# CurrentSources.net
KiCad netlist of a schematic drawn in Altium Designer
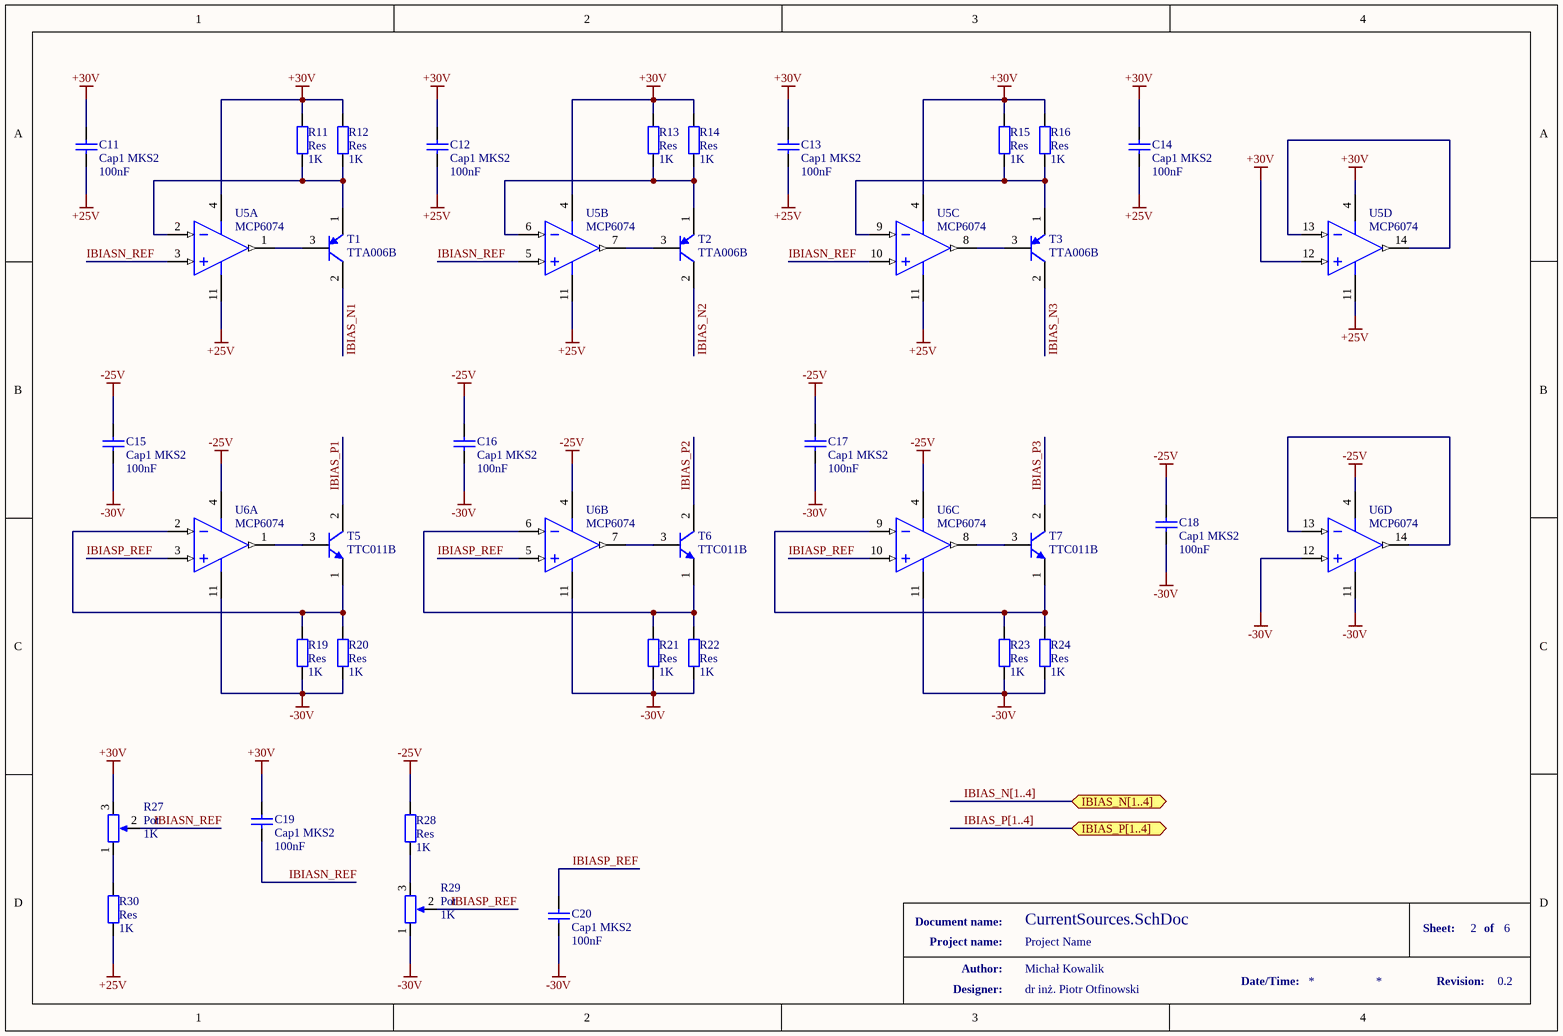
[diagram p0: CurrentSources.SchDoc]

(export (version "E")
  (design (tool "Eeschema 10.0.6"))
  (components
    (comp (ref "C11")
      (value "Cap1 MKS2")
      (footprint "CAP-0.5-WIMA_MKS2")
      (description "WIMA MKS2 Metallized Polyester (PET) \r\nCapacitors in PCM 5 mm")
      (fields (field (name "ALTIUM_VALUE") "100nF"))
      (libsource (lib "SchematicLib") (part "Cap1"))
    )
    (comp (ref "C12")
      (value "Cap1 MKS2")
      (footprint "CAP-0.5-WIMA_MKS2")
      (description "WIMA MKS2 Metallized Polyester (PET) \r\nCapacitors in PCM 5 mm")
      (fields (field (name "ALTIUM_VALUE") "100nF"))
      (libsource (lib "SchematicLib") (part "Cap1"))
    )
    (comp (ref "C13")
      (value "Cap1 MKS2")
      (footprint "CAP-0.5-WIMA_MKS2")
      (description "WIMA MKS2 Metallized Polyester (PET) \r\nCapacitors in PCM 5 mm")
      (fields (field (name "ALTIUM_VALUE") "100nF"))
      (libsource (lib "SchematicLib") (part "Cap1"))
    )
    (comp (ref "C14")
      (value "Cap1 MKS2")
      (footprint "CAP-0.5-WIMA_MKS2")
      (description "WIMA MKS2 Metallized Polyester (PET) \r\nCapacitors in PCM 5 mm")
      (fields (field (name "ALTIUM_VALUE") "100nF"))
      (libsource (lib "SchematicLib") (part "Cap1"))
    )
    (comp (ref "C15")
      (value "Cap1 MKS2")
      (footprint "CAP-0.5-WIMA_MKS2")
      (description "WIMA MKS2 Metallized Polyester (PET) \r\nCapacitors in PCM 5 mm")
      (fields (field (name "ALTIUM_VALUE") "100nF"))
      (libsource (lib "SchematicLib") (part "Cap1"))
    )
    (comp (ref "C16")
      (value "Cap1 MKS2")
      (footprint "CAP-0.5-WIMA_MKS2")
      (description "WIMA MKS2 Metallized Polyester (PET) \r\nCapacitors in PCM 5 mm")
      (fields (field (name "ALTIUM_VALUE") "100nF"))
      (libsource (lib "SchematicLib") (part "Cap1"))
    )
    (comp (ref "C17")
      (value "Cap1 MKS2")
      (footprint "CAP-0.5-WIMA_MKS2")
      (description "WIMA MKS2 Metallized Polyester (PET) \r\nCapacitors in PCM 5 mm")
      (fields (field (name "ALTIUM_VALUE") "100nF"))
      (libsource (lib "SchematicLib") (part "Cap1"))
    )
    (comp (ref "C18")
      (value "Cap1 MKS2")
      (footprint "CAP-0.5-WIMA_MKS2")
      (description "WIMA MKS2 Metallized Polyester (PET) \r\nCapacitors in PCM 5 mm")
      (fields (field (name "ALTIUM_VALUE") "100nF"))
      (libsource (lib "SchematicLib") (part "Cap1"))
    )
    (comp (ref "C19")
      (value "Cap1 MKS2")
      (footprint "CAP-0.5-WIMA_MKS2")
      (description "WIMA MKS2 Metallized Polyester (PET) \r\nCapacitors in PCM 5 mm")
      (fields (field (name "ALTIUM_VALUE") "100nF"))
      (libsource (lib "SchematicLib") (part "Cap1"))
    )
    (comp (ref "C20")
      (value "Cap1 MKS2")
      (footprint "CAP-0.5-WIMA_MKS2")
      (description "WIMA MKS2 Metallized Polyester (PET) \r\nCapacitors in PCM 5 mm")
      (fields (field (name "ALTIUM_VALUE") "100nF"))
      (libsource (lib "SchematicLib") (part "Cap1"))
    )
    (comp (ref "R11")
      (value "Res")
      (footprint "RESISTOR-10mm")
      (description "Resistor")
      (fields (field (name "ALTIUM_VALUE") "1K"))
      (libsource (lib "SchematicLib") (part "Res"))
    )
    (comp (ref "R12")
      (value "Res")
      (footprint "RESISTOR-10mm")
      (description "Resistor")
      (fields (field (name "ALTIUM_VALUE") "1K"))
      (libsource (lib "SchematicLib") (part "Res"))
    )
    (comp (ref "R13")
      (value "Res")
      (footprint "RESISTOR-10mm")
      (description "Resistor")
      (fields (field (name "ALTIUM_VALUE") "1K"))
      (libsource (lib "SchematicLib") (part "Res"))
    )
    (comp (ref "R14")
      (value "Res")
      (footprint "RESISTOR-10mm")
      (description "Resistor")
      (fields (field (name "ALTIUM_VALUE") "1K"))
      (libsource (lib "SchematicLib") (part "Res"))
    )
    (comp (ref "R15")
      (value "Res")
      (footprint "RESISTOR-10mm")
      (description "Resistor")
      (fields (field (name "ALTIUM_VALUE") "1K"))
      (libsource (lib "SchematicLib") (part "Res"))
    )
    (comp (ref "R16")
      (value "Res")
      (footprint "RESISTOR-10mm")
      (description "Resistor")
      (fields (field (name "ALTIUM_VALUE") "1K"))
      (libsource (lib "SchematicLib") (part "Res"))
    )
    (comp (ref "R19")
      (value "Res")
      (footprint "RESISTOR-10mm")
      (description "Resistor")
      (fields (field (name "ALTIUM_VALUE") "1K"))
      (libsource (lib "SchematicLib") (part "Res"))
    )
    (comp (ref "R20")
      (value "Res")
      (footprint "RESISTOR-10mm")
      (description "Resistor")
      (fields (field (name "ALTIUM_VALUE") "1K"))
      (libsource (lib "SchematicLib") (part "Res"))
    )
    (comp (ref "R21")
      (value "Res")
      (footprint "RESISTOR-10mm")
      (description "Resistor")
      (fields (field (name "ALTIUM_VALUE") "1K"))
      (libsource (lib "SchematicLib") (part "Res"))
    )
    (comp (ref "R22")
      (value "Res")
      (footprint "RESISTOR-10mm")
      (description "Resistor")
      (fields (field (name "ALTIUM_VALUE") "1K"))
      (libsource (lib "SchematicLib") (part "Res"))
    )
    (comp (ref "R23")
      (value "Res")
      (footprint "RESISTOR-10mm")
      (description "Resistor")
      (fields (field (name "ALTIUM_VALUE") "1K"))
      (libsource (lib "SchematicLib") (part "Res"))
    )
    (comp (ref "R24")
      (value "Res")
      (footprint "RESISTOR-10mm")
      (description "Resistor")
      (fields (field (name "ALTIUM_VALUE") "1K"))
      (libsource (lib "SchematicLib") (part "Res"))
    )
    (comp (ref "R27")
      (value "Pot")
      (footprint "T910W")
      (description "Potentiometer")
      (fields (field (name "ALTIUM_VALUE") "1K"))
      (libsource (lib "SchematicLib") (part "Pot"))
    )
    (comp (ref "R28")
      (value "Res")
      (footprint "RESISTOR-10mm")
      (description "Resistor")
      (fields (field (name "ALTIUM_VALUE") "1K"))
      (libsource (lib "SchematicLib") (part "Res"))
    )
    (comp (ref "R29")
      (value "Pot")
      (footprint "T910W")
      (description "Potentiometer")
      (fields (field (name "ALTIUM_VALUE") "1K"))
      (libsource (lib "SchematicLib") (part "Pot"))
    )
    (comp (ref "R30")
      (value "Res")
      (footprint "RESISTOR-10mm")
      (description "Resistor")
      (fields (field (name "ALTIUM_VALUE") "1K"))
      (libsource (lib "SchematicLib") (part "Res"))
    )
    (comp (ref "T1")
      (value "TTA006B")
      (footprint "TO-126")
      (description "PNP High Voltage Transistor")
      (libsource (lib "SchematicLib") (part "TTA006B"))
    )
    (comp (ref "T2")
      (value "TTA006B")
      (footprint "TO-126")
      (description "PNP High Voltage Transistor")
      (libsource (lib "SchematicLib") (part "TTA006B"))
    )
    (comp (ref "T3")
      (value "TTA006B")
      (footprint "TO-126")
      (description "PNP High Voltage Transistor")
      (libsource (lib "SchematicLib") (part "TTA006B"))
    )
    (comp (ref "T5")
      (value "TTC011B")
      (footprint "TO-126")
      (description "NPN High Voltage Transistor")
      (libsource (lib "SchematicLib") (part "TTC011B"))
    )
    (comp (ref "T6")
      (value "TTC011B")
      (footprint "TO-126")
      (description "NPN High Voltage Transistor")
      (libsource (lib "SchematicLib") (part "TTC011B"))
    )
    (comp (ref "T7")
      (value "TTC011B")
      (footprint "TO-126")
      (description "NPN High Voltage Transistor")
      (libsource (lib "SchematicLib") (part "TTC011B"))
    )
    (comp (ref "U5")
      (value "MCP6074")
      (footprint "SO_14_IPC_MD")
      (description "110 µA, High Precision Quad Op Amp, 14-Pin SOIC, Extended Temperature, Tape and Reel")
      (fields (field (name "PUBLISHER") "Altium Limited"))
      (libsource (lib "SchematicLib") (part "MCP6074"))
    )
    (comp (ref "U6")
      (value "MCP6074")
      (footprint "SO_14_IPC_MD")
      (description "110 µA, High Precision Quad Op Amp, 14-Pin SOIC, Extended Temperature, Tape and Reel")
      (fields (field (name "PUBLISHER") "Altium Limited"))
      (libsource (lib "SchematicLib") (part "MCP6074"))
    )
  )
  (nets
    (net (code "3") (name "+25V") (class "Default")
      (node (ref "C11") (pin "1") (pinfunction "1_1") (pintype "passive"))
      (node (ref "C12") (pin "1") (pinfunction "1_1") (pintype "passive"))
      (node (ref "C13") (pin "1") (pinfunction "1_1") (pintype "passive"))
      (node (ref "C14") (pin "1") (pinfunction "1_1") (pintype "passive"))
      (node (ref "R30") (pin "1") (pinfunction "1_1") (pintype "passive"))
      (node (ref "U5") (pin "11") (pinfunction "VSS_11") (pintype "power_in"))
    )
    (net (code "4") (name "+30V") (class "Default")
      (node (ref "C11") (pin "2") (pinfunction "2_2") (pintype "passive"))
      (node (ref "C12") (pin "2") (pinfunction "2_2") (pintype "passive"))
      (node (ref "C13") (pin "2") (pinfunction "2_2") (pintype "passive"))
      (node (ref "C14") (pin "2") (pinfunction "2_2") (pintype "passive"))
      (node (ref "C19") (pin "2") (pinfunction "2_2") (pintype "passive"))
      (node (ref "R11") (pin "2") (pinfunction "2_2") (pintype "passive"))
      (node (ref "R12") (pin "2") (pinfunction "2_2") (pintype "passive"))
      (node (ref "R13") (pin "2") (pinfunction "2_2") (pintype "passive"))
      (node (ref "R14") (pin "2") (pinfunction "2_2") (pintype "passive"))
      (node (ref "R15") (pin "2") (pinfunction "2_2") (pintype "passive"))
      (node (ref "R16") (pin "2") (pinfunction "2_2") (pintype "passive"))
      (node (ref "R27") (pin "3") (pinfunction "3_3") (pintype "passive"))
      (node (ref "U5") (pin "12") (pinfunction "VIND+_12") (pintype "input"))
      (node (ref "U5") (pin "4") (pinfunction "VDD_4") (pintype "power_in"))
    )
    (net (code "5") (name "-25V") (class "Default")
      (node (ref "C15") (pin "2") (pinfunction "2_2") (pintype "passive"))
      (node (ref "C16") (pin "2") (pinfunction "2_2") (pintype "passive"))
      (node (ref "C17") (pin "2") (pinfunction "2_2") (pintype "passive"))
      (node (ref "C18") (pin "2") (pinfunction "2_2") (pintype "passive"))
      (node (ref "R28") (pin "2") (pinfunction "2_2") (pintype "passive"))
      (node (ref "U6") (pin "4") (pinfunction "VDD_4") (pintype "power_in"))
    )
    (net (code "6") (name "-30V") (class "Default")
      (node (ref "C15") (pin "1") (pinfunction "1_1") (pintype "passive"))
      (node (ref "C16") (pin "1") (pinfunction "1_1") (pintype "passive"))
      (node (ref "C17") (pin "1") (pinfunction "1_1") (pintype "passive"))
      (node (ref "C18") (pin "1") (pinfunction "1_1") (pintype "passive"))
      (node (ref "C20") (pin "1") (pinfunction "1_1") (pintype "passive"))
      (node (ref "R19") (pin "1") (pinfunction "1_1") (pintype "passive"))
      (node (ref "R20") (pin "1") (pinfunction "1_1") (pintype "passive"))
      (node (ref "R21") (pin "1") (pinfunction "1_1") (pintype "passive"))
      (node (ref "R22") (pin "1") (pinfunction "1_1") (pintype "passive"))
      (node (ref "R23") (pin "1") (pinfunction "1_1") (pintype "passive"))
      (node (ref "R24") (pin "1") (pinfunction "1_1") (pintype "passive"))
      (node (ref "R29") (pin "1") (pinfunction "1_1") (pintype "passive"))
      (node (ref "U6") (pin "11") (pinfunction "VSS_11") (pintype "power_in"))
      (node (ref "U6") (pin "12") (pinfunction "VIND+_12") (pintype "input"))
    )
    (net (code "7") (name "/IBIASN_REF") (class "Default")
      (node (ref "C19") (pin "1") (pinfunction "1_1") (pintype "passive"))
      (node (ref "R27") (pin "2") (pinfunction "2_2") (pintype "passive"))
      (node (ref "U5") (pin "10") (pinfunction "VINC+_10") (pintype "input"))
      (node (ref "U5") (pin "3") (pinfunction "VINA+_3") (pintype "input"))
      (node (ref "U5") (pin "5") (pinfunction "VINB+_5") (pintype "input"))
    )
    (net (code "8") (name "/IBIASP_REF") (class "Default")
      (node (ref "C20") (pin "2") (pinfunction "2_2") (pintype "passive"))
      (node (ref "R29") (pin "2") (pinfunction "2_2") (pintype "passive"))
      (node (ref "U6") (pin "10") (pinfunction "VINC+_10") (pintype "input"))
      (node (ref "U6") (pin "3") (pinfunction "VINA+_3") (pintype "input"))
      (node (ref "U6") (pin "5") (pinfunction "VINB+_5") (pintype "input"))
    )
    (net (code "9") (name "/IBIAS_N1") (class "Default")
      (node (ref "T1") (pin "2") (pinfunction "C_2") (pintype "passive"))
    )
    (net (code "10") (name "/IBIAS_N2") (class "Default")
      (node (ref "T2") (pin "2") (pinfunction "C_2") (pintype "passive"))
    )
    (net (code "11") (name "/IBIAS_N3") (class "Default")
      (node (ref "T3") (pin "2") (pinfunction "C_2") (pintype "passive"))
    )
    (net (code "13") (name "/IBIAS_P1") (class "Default")
      (node (ref "T5") (pin "2") (pinfunction "C_2") (pintype "passive"))
    )
    (net (code "14") (name "/IBIAS_P2") (class "Default")
      (node (ref "T6") (pin "2") (pinfunction "C_2") (pintype "passive"))
    )
    (net (code "15") (name "/IBIAS_P3") (class "Default")
      (node (ref "T7") (pin "2") (pinfunction "C_2") (pintype "passive"))
    )
    (net (code "17") (name "Net-(R27-Pad1)") (class "Default")
      (node (ref "R27") (pin "1") (pinfunction "1_1") (pintype "passive"))
      (node (ref "R30") (pin "2") (pinfunction "2_2") (pintype "passive"))
    )
    (net (code "18") (name "Net-(R28-Pad1)") (class "Default")
      (node (ref "R28") (pin "1") (pinfunction "1_1") (pintype "passive"))
      (node (ref "R29") (pin "3") (pinfunction "3_3") (pintype "passive"))
    )
    (net (code "19") (name "Net-(T1-B)") (class "Default")
      (node (ref "T1") (pin "3") (pinfunction "B_3") (pintype "passive"))
      (node (ref "U5") (pin "1") (pinfunction "VOUTA_1") (pintype "output"))
    )
    (net (code "20") (name "Net-(T1-E)") (class "Default")
      (node (ref "R11") (pin "1") (pinfunction "1_1") (pintype "passive"))
      (node (ref "R12") (pin "1") (pinfunction "1_1") (pintype "passive"))
      (node (ref "T1") (pin "1") (pinfunction "E_1") (pintype "passive"))
      (node (ref "U5") (pin "2") (pinfunction "VINA-_2") (pintype "input"))
    )
    (net (code "21") (name "Net-(T2-B)") (class "Default")
      (node (ref "T2") (pin "3") (pinfunction "B_3") (pintype "passive"))
      (node (ref "U5") (pin "7") (pinfunction "VOUTB_7") (pintype "output"))
    )
    (net (code "22") (name "Net-(T2-E)") (class "Default")
      (node (ref "R13") (pin "1") (pinfunction "1_1") (pintype "passive"))
      (node (ref "R14") (pin "1") (pinfunction "1_1") (pintype "passive"))
      (node (ref "T2") (pin "1") (pinfunction "E_1") (pintype "passive"))
      (node (ref "U5") (pin "6") (pinfunction "VINB-_6") (pintype "input"))
    )
    (net (code "23") (name "Net-(T3-B)") (class "Default")
      (node (ref "T3") (pin "3") (pinfunction "B_3") (pintype "passive"))
      (node (ref "U5") (pin "8") (pinfunction "VOUTC_8") (pintype "output"))
    )
    (net (code "24") (name "Net-(T3-E)") (class "Default")
      (node (ref "R15") (pin "1") (pinfunction "1_1") (pintype "passive"))
      (node (ref "R16") (pin "1") (pinfunction "1_1") (pintype "passive"))
      (node (ref "T3") (pin "1") (pinfunction "E_1") (pintype "passive"))
      (node (ref "U5") (pin "9") (pinfunction "VINC-_9") (pintype "input"))
    )
    (net (code "25") (name "Net-(T5-B)") (class "Default")
      (node (ref "T5") (pin "3") (pinfunction "B_3") (pintype "passive"))
      (node (ref "U6") (pin "1") (pinfunction "VOUTA_1") (pintype "output"))
    )
    (net (code "26") (name "Net-(T5-E)") (class "Default")
      (node (ref "R19") (pin "2") (pinfunction "2_2") (pintype "passive"))
      (node (ref "R20") (pin "2") (pinfunction "2_2") (pintype "passive"))
      (node (ref "T5") (pin "1") (pinfunction "E_1") (pintype "passive"))
      (node (ref "U6") (pin "2") (pinfunction "VINA-_2") (pintype "input"))
    )
    (net (code "27") (name "Net-(T6-B)") (class "Default")
      (node (ref "T6") (pin "3") (pinfunction "B_3") (pintype "passive"))
      (node (ref "U6") (pin "7") (pinfunction "VOUTB_7") (pintype "output"))
    )
    (net (code "28") (name "Net-(T6-E)") (class "Default")
      (node (ref "R21") (pin "2") (pinfunction "2_2") (pintype "passive"))
      (node (ref "R22") (pin "2") (pinfunction "2_2") (pintype "passive"))
      (node (ref "T6") (pin "1") (pinfunction "E_1") (pintype "passive"))
      (node (ref "U6") (pin "6") (pinfunction "VINB-_6") (pintype "input"))
    )
    (net (code "29") (name "Net-(T7-B)") (class "Default")
      (node (ref "T7") (pin "3") (pinfunction "B_3") (pintype "passive"))
      (node (ref "U6") (pin "8") (pinfunction "VOUTC_8") (pintype "output"))
    )
    (net (code "30") (name "Net-(T7-E)") (class "Default")
      (node (ref "R23") (pin "2") (pinfunction "2_2") (pintype "passive"))
      (node (ref "R24") (pin "2") (pinfunction "2_2") (pintype "passive"))
      (node (ref "T7") (pin "1") (pinfunction "E_1") (pintype "passive"))
      (node (ref "U6") (pin "9") (pinfunction "VINC-_9") (pintype "input"))
    )
    (net (code "31") (name "Net-(U5D-VIND-)") (class "Default")
      (node (ref "U5") (pin "13") (pinfunction "VIND-_13") (pintype "input"))
      (node (ref "U5") (pin "14") (pinfunction "VOUTD_14") (pintype "output"))
    )
    (net (code "32") (name "Net-(U6D-VIND-)") (class "Default")
      (node (ref "U6") (pin "13") (pinfunction "VIND-_13") (pintype "input"))
      (node (ref "U6") (pin "14") (pinfunction "VOUTD_14") (pintype "output"))
    )
  )
)
